# LEDs.net
KiCad netlist of a schematic drawn in Altium Designer
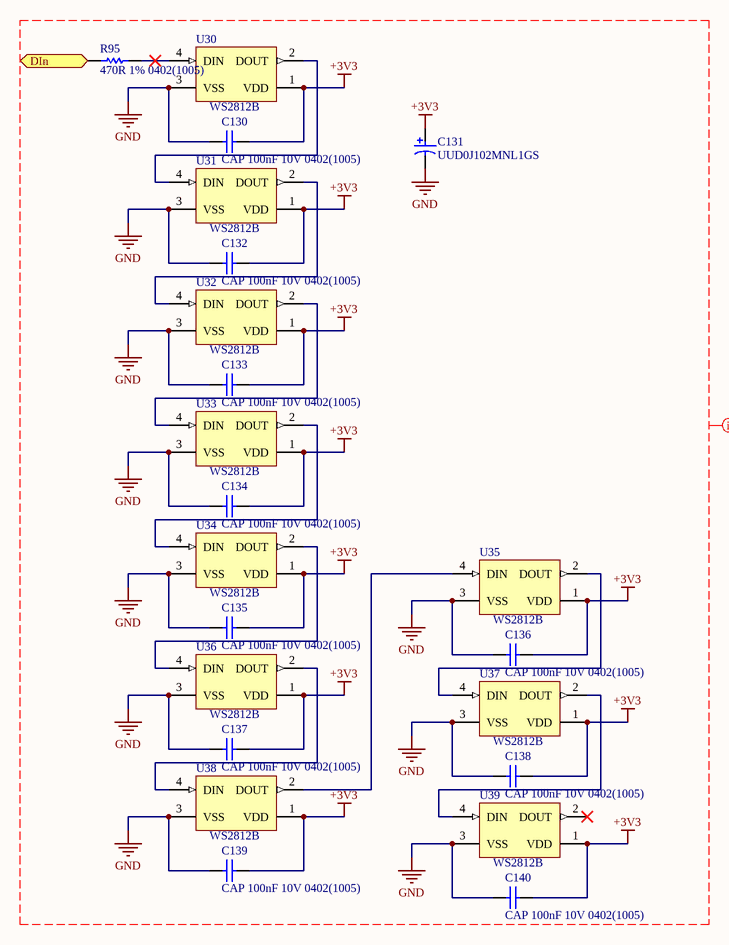
[diagram p0: LEDs.SchDoc]

(export (version "E")
  (design (tool "Eeschema 10.0.6"))
  (components
    (comp (ref "C130")
      (value "CAP 100nF 10V 0402(1005)")
      (footprint "CAPC0402(1005)60_L")
      (description "CAP 100nF 10V ±20% 0402 (1005 Metric) Thickness 0.6mm SMD")
      (fields (field (name "TOLERANCE") "Â±20%"))
      (libsource (lib "Altium Content Vault") (part "CAP"))
    )
    (comp (ref "C131")
      (value "UUD0J102MNL1GS")
      (footprint "NIC-CAPA2-8X10_V")
      (fields (field (name "MANUFACTURER") "Nichicon"))
      (libsource (lib "Altium Content Vault") (part "NIC-CAP-P-2"))
    )
    (comp (ref "C132")
      (value "CAP 100nF 10V 0402(1005)")
      (footprint "CAPC0402(1005)60_L")
      (description "CAP 100nF 10V ±20% 0402 (1005 Metric) Thickness 0.6mm SMD")
      (fields (field (name "TOLERANCE") "Â±20%"))
      (libsource (lib "Altium Content Vault") (part "CAP"))
    )
    (comp (ref "C133")
      (value "CAP 100nF 10V 0402(1005)")
      (footprint "CAPC0402(1005)60_L")
      (description "CAP 100nF 10V ±20% 0402 (1005 Metric) Thickness 0.6mm SMD")
      (fields (field (name "TOLERANCE") "Â±20%"))
      (libsource (lib "Altium Content Vault") (part "CAP"))
    )
    (comp (ref "C134")
      (value "CAP 100nF 10V 0402(1005)")
      (footprint "CAPC0402(1005)60_L")
      (description "CAP 100nF 10V ±20% 0402 (1005 Metric) Thickness 0.6mm SMD")
      (fields (field (name "TOLERANCE") "Â±20%"))
      (libsource (lib "Altium Content Vault") (part "CAP"))
    )
    (comp (ref "C135")
      (value "CAP 100nF 10V 0402(1005)")
      (footprint "CAPC0402(1005)60_L")
      (description "CAP 100nF 10V ±20% 0402 (1005 Metric) Thickness 0.6mm SMD")
      (fields (field (name "TOLERANCE") "Â±20%"))
      (libsource (lib "Altium Content Vault") (part "CAP"))
    )
    (comp (ref "C136")
      (value "CAP 100nF 10V 0402(1005)")
      (footprint "CAPC0402(1005)60_L")
      (description "CAP 100nF 10V ±20% 0402 (1005 Metric) Thickness 0.6mm SMD")
      (fields (field (name "TOLERANCE") "Â±20%"))
      (libsource (lib "Altium Content Vault") (part "CAP"))
    )
    (comp (ref "C137")
      (value "CAP 100nF 10V 0402(1005)")
      (footprint "CAPC0402(1005)60_L")
      (description "CAP 100nF 10V ±20% 0402 (1005 Metric) Thickness 0.6mm SMD")
      (fields (field (name "TOLERANCE") "Â±20%"))
      (libsource (lib "Altium Content Vault") (part "CAP"))
    )
    (comp (ref "C138")
      (value "CAP 100nF 10V 0402(1005)")
      (footprint "CAPC0402(1005)60_L")
      (description "CAP 100nF 10V ±20% 0402 (1005 Metric) Thickness 0.6mm SMD")
      (fields (field (name "TOLERANCE") "Â±20%"))
      (libsource (lib "Altium Content Vault") (part "CAP"))
    )
    (comp (ref "C139")
      (value "CAP 100nF 10V 0402(1005)")
      (footprint "CAPC0402(1005)60_L")
      (description "CAP 100nF 10V ±20% 0402 (1005 Metric) Thickness 0.6mm SMD")
      (fields (field (name "TOLERANCE") "Â±20%"))
      (libsource (lib "Altium Content Vault") (part "CAP"))
    )
    (comp (ref "C140")
      (value "CAP 100nF 10V 0402(1005)")
      (footprint "CAPC0402(1005)60_L")
      (description "CAP 100nF 10V ±20% 0402 (1005 Metric) Thickness 0.6mm SMD")
      (fields (field (name "TOLERANCE") "Â±20%"))
      (libsource (lib "Altium Content Vault") (part "CAP"))
    )
    (comp (ref "R95")
      (value "470R 1% 0402(1005)")
      (footprint "RESC0402(1005)_L")
      (description "470R 0.063W 1% 0402 (1005 Metric)  SMD")
      (fields (field (name "TOLERANCE") "1 %") (field (name "POWER") "0.063 W"))
      (libsource (lib "Altium Content Vault") (part "RES"))
    )
    (comp (ref "U30")
      (value "WS2812B")
      (footprint "ADAI-WS2812B_V")
      (fields (field (name "TOLERANCE") "10%"))
      (libsource (lib "Altium Content Vault") (part "ADAI-WS2812B-4"))
    )
    (comp (ref "U31")
      (value "WS2812B")
      (footprint "ADAI-WS2812B_V")
      (fields (field (name "TOLERANCE") "10%"))
      (libsource (lib "Altium Content Vault") (part "ADAI-WS2812B-4"))
    )
    (comp (ref "U32")
      (value "WS2812B")
      (footprint "ADAI-WS2812B_V")
      (fields (field (name "TOLERANCE") "10%"))
      (libsource (lib "Altium Content Vault") (part "ADAI-WS2812B-4"))
    )
    (comp (ref "U33")
      (value "WS2812B")
      (footprint "ADAI-WS2812B_V")
      (fields (field (name "TOLERANCE") "10%"))
      (libsource (lib "Altium Content Vault") (part "ADAI-WS2812B-4"))
    )
    (comp (ref "U34")
      (value "WS2812B")
      (footprint "ADAI-WS2812B_V")
      (fields (field (name "TOLERANCE") "10%"))
      (libsource (lib "Altium Content Vault") (part "ADAI-WS2812B-4"))
    )
    (comp (ref "U35")
      (value "WS2812B")
      (footprint "ADAI-WS2812B_V")
      (fields (field (name "TOLERANCE") "10%"))
      (libsource (lib "Altium Content Vault") (part "ADAI-WS2812B-4"))
    )
    (comp (ref "U36")
      (value "WS2812B")
      (footprint "ADAI-WS2812B_V")
      (fields (field (name "TOLERANCE") "10%"))
      (libsource (lib "Altium Content Vault") (part "ADAI-WS2812B-4"))
    )
    (comp (ref "U37")
      (value "WS2812B")
      (footprint "ADAI-WS2812B_V")
      (fields (field (name "TOLERANCE") "10%"))
      (libsource (lib "Altium Content Vault") (part "ADAI-WS2812B-4"))
    )
    (comp (ref "U38")
      (value "WS2812B")
      (footprint "ADAI-WS2812B_V")
      (fields (field (name "TOLERANCE") "10%"))
      (libsource (lib "Altium Content Vault") (part "ADAI-WS2812B-4"))
    )
    (comp (ref "U39")
      (value "WS2812B")
      (footprint "ADAI-WS2812B_V")
      (fields (field (name "TOLERANCE") "10%"))
      (libsource (lib "Altium Content Vault") (part "ADAI-WS2812B-4"))
    )
  )
  (nets
    (net (code "1") (name "+3V3") (class "Default")
      (node (ref "C130") (pin "1") (pinfunction "1_1") (pintype "passive"))
      (node (ref "C131") (pin "1") (pinfunction "1_1") (pintype "passive"))
      (node (ref "C132") (pin "1") (pinfunction "1_1") (pintype "passive"))
      (node (ref "C133") (pin "1") (pinfunction "1_1") (pintype "passive"))
      (node (ref "C134") (pin "1") (pinfunction "1_1") (pintype "passive"))
      (node (ref "C135") (pin "1") (pinfunction "1_1") (pintype "passive"))
      (node (ref "C136") (pin "1") (pinfunction "1_1") (pintype "passive"))
      (node (ref "C137") (pin "1") (pinfunction "1_1") (pintype "passive"))
      (node (ref "C138") (pin "1") (pinfunction "1_1") (pintype "passive"))
      (node (ref "C139") (pin "1") (pinfunction "1_1") (pintype "passive"))
      (node (ref "C140") (pin "1") (pinfunction "1_1") (pintype "passive"))
      (node (ref "U30") (pin "1") (pinfunction "VDD_1") (pintype "power_in"))
      (node (ref "U31") (pin "1") (pinfunction "VDD_1") (pintype "power_in"))
      (node (ref "U32") (pin "1") (pinfunction "VDD_1") (pintype "power_in"))
      (node (ref "U33") (pin "1") (pinfunction "VDD_1") (pintype "power_in"))
      (node (ref "U34") (pin "1") (pinfunction "VDD_1") (pintype "power_in"))
      (node (ref "U35") (pin "1") (pinfunction "VDD_1") (pintype "power_in"))
      (node (ref "U36") (pin "1") (pinfunction "VDD_1") (pintype "power_in"))
      (node (ref "U37") (pin "1") (pinfunction "VDD_1") (pintype "power_in"))
      (node (ref "U38") (pin "1") (pinfunction "VDD_1") (pintype "power_in"))
      (node (ref "U39") (pin "1") (pinfunction "VDD_1") (pintype "power_in"))
    )
    (net (code "2") (name "/DIn") (class "Default")
      (node (ref "R95") (pin "1") (pinfunction "1_1") (pintype "passive"))
    )
    (net (code "3") (name "GND") (class "Default")
      (node (ref "C130") (pin "2") (pinfunction "2_2") (pintype "passive"))
      (node (ref "C131") (pin "2") (pinfunction "2_2") (pintype "passive"))
      (node (ref "C132") (pin "2") (pinfunction "2_2") (pintype "passive"))
      (node (ref "C133") (pin "2") (pinfunction "2_2") (pintype "passive"))
      (node (ref "C134") (pin "2") (pinfunction "2_2") (pintype "passive"))
      (node (ref "C135") (pin "2") (pinfunction "2_2") (pintype "passive"))
      (node (ref "C136") (pin "2") (pinfunction "2_2") (pintype "passive"))
      (node (ref "C137") (pin "2") (pinfunction "2_2") (pintype "passive"))
      (node (ref "C138") (pin "2") (pinfunction "2_2") (pintype "passive"))
      (node (ref "C139") (pin "2") (pinfunction "2_2") (pintype "passive"))
      (node (ref "C140") (pin "2") (pinfunction "2_2") (pintype "passive"))
      (node (ref "U30") (pin "3") (pinfunction "VSS_3") (pintype "power_in"))
      (node (ref "U31") (pin "3") (pinfunction "VSS_3") (pintype "power_in"))
      (node (ref "U32") (pin "3") (pinfunction "VSS_3") (pintype "power_in"))
      (node (ref "U33") (pin "3") (pinfunction "VSS_3") (pintype "power_in"))
      (node (ref "U34") (pin "3") (pinfunction "VSS_3") (pintype "power_in"))
      (node (ref "U35") (pin "3") (pinfunction "VSS_3") (pintype "power_in"))
      (node (ref "U36") (pin "3") (pinfunction "VSS_3") (pintype "power_in"))
      (node (ref "U37") (pin "3") (pinfunction "VSS_3") (pintype "power_in"))
      (node (ref "U38") (pin "3") (pinfunction "VSS_3") (pintype "power_in"))
      (node (ref "U39") (pin "3") (pinfunction "VSS_3") (pintype "power_in"))
    )
    (net (code "4") (name "Net-(U30-DIN)") (class "Default")
      (node (ref "R95") (pin "2") (pinfunction "2_2") (pintype "passive"))
      (node (ref "U30") (pin "4") (pinfunction "DIN_4") (pintype "input"))
    )
    (net (code "5") (name "Net-(U30-DOUT)") (class "Default")
      (node (ref "U30") (pin "2") (pinfunction "DOUT_2") (pintype "output"))
      (node (ref "U31") (pin "4") (pinfunction "DIN_4") (pintype "input"))
    )
    (net (code "6") (name "Net-(U31-DOUT)") (class "Default")
      (node (ref "U31") (pin "2") (pinfunction "DOUT_2") (pintype "output"))
      (node (ref "U32") (pin "4") (pinfunction "DIN_4") (pintype "input"))
    )
    (net (code "7") (name "Net-(U32-DOUT)") (class "Default")
      (node (ref "U32") (pin "2") (pinfunction "DOUT_2") (pintype "output"))
      (node (ref "U33") (pin "4") (pinfunction "DIN_4") (pintype "input"))
    )
    (net (code "8") (name "Net-(U33-DOUT)") (class "Default")
      (node (ref "U33") (pin "2") (pinfunction "DOUT_2") (pintype "output"))
      (node (ref "U34") (pin "4") (pinfunction "DIN_4") (pintype "input"))
    )
    (net (code "9") (name "Net-(U34-DOUT)") (class "Default")
      (node (ref "U34") (pin "2") (pinfunction "DOUT_2") (pintype "output"))
      (node (ref "U36") (pin "4") (pinfunction "DIN_4") (pintype "input"))
    )
    (net (code "10") (name "Net-(U35-DIN)") (class "Default")
      (node (ref "U35") (pin "4") (pinfunction "DIN_4") (pintype "input"))
      (node (ref "U38") (pin "2") (pinfunction "DOUT_2") (pintype "output"))
    )
    (net (code "11") (name "Net-(U35-DOUT)") (class "Default")
      (node (ref "U35") (pin "2") (pinfunction "DOUT_2") (pintype "output"))
      (node (ref "U37") (pin "4") (pinfunction "DIN_4") (pintype "input"))
    )
    (net (code "12") (name "Net-(U36-DOUT)") (class "Default")
      (node (ref "U36") (pin "2") (pinfunction "DOUT_2") (pintype "output"))
      (node (ref "U38") (pin "4") (pinfunction "DIN_4") (pintype "input"))
    )
    (net (code "13") (name "Net-(U37-DOUT)") (class "Default")
      (node (ref "U37") (pin "2") (pinfunction "DOUT_2") (pintype "output"))
      (node (ref "U39") (pin "4") (pinfunction "DIN_4") (pintype "input"))
    )
    (net (code "14") (name "unconnected-(U39-DOUT-Pad2)") (class "Default")
      (node (ref "U39") (pin "2") (pinfunction "DOUT_2") (pintype "output+no_connect"))
    )
  )
)
